# rasp_infrad.net
KiCad netlist of a schematic drawn in Altium Designer
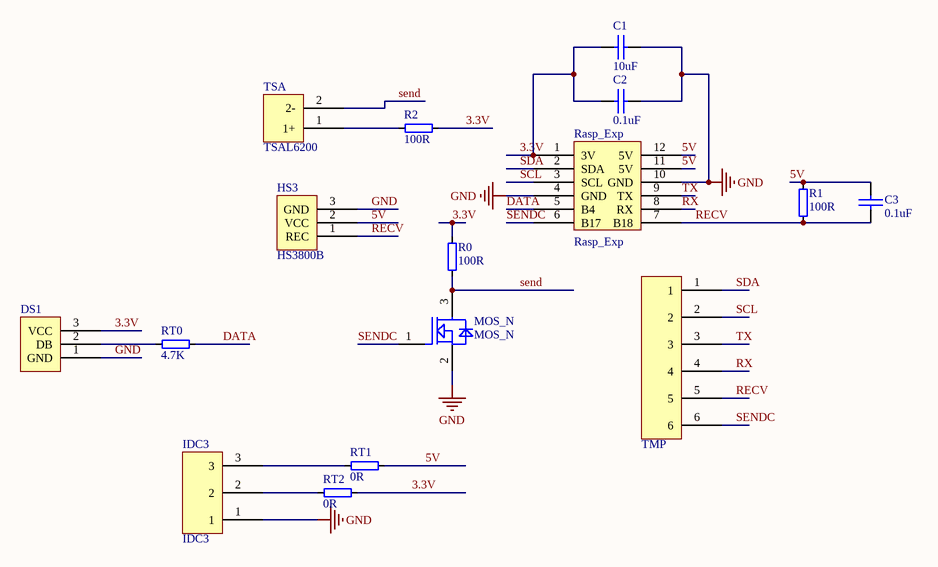
[diagram p0: rasp_infrad.SchDoc]

(export (version "E")
  (design (tool "Eeschema 10.0.6"))
  (components
    (comp (ref "C1")
      (value "10uF")
      (footprint "0805")
      (description "Capacitor")
      (libsource (lib "电容") (part "普通电容"))
    )
    (comp (ref "C2")
      (value "0.1uF")
      (footprint "0805")
      (description "Capacitor")
      (libsource (lib "电容") (part "普通电容"))
    )
    (comp (ref "C3")
      (value "0.1uF")
      (footprint "0805")
      (description "Capacitor")
      (libsource (lib "电容") (part "普通电容"))
    )
    (comp (ref "DS1")
      (value "DS1")
      (footprint "DS18B20")
      (description "数字温度传感器")
      (libsource (lib "Mo1-三角") (part "DS18B20"))
    )
    (comp (ref "HS3")
      (value "HS3800B")
      (footprint "HS0038B")
      (description "红外接收管")
      (libsource (lib "Mo1-三角") (part "HS3800B"))
    )
    (comp (ref "IDC3") (value "IDC3") (footprint "IDC3") (libsource (lib "Mo1-三角") (part "三脚引线孔")))
    (comp (ref "MOS_N") (value "MOS_N") (footprint "MOSN") (libsource (lib "Mo1-三角") (part "MOS_N")))
    (comp (ref "R0") (value "100R") (footprint "0805") (libsource (lib "电阻") (part "RES")))
    (comp (ref "R1") (value "100R") (footprint "0805") (libsource (lib "电阻") (part "RES")))
    (comp (ref "R2") (value "100R") (footprint "0805") (libsource (lib "电阻") (part "RES")))
    (comp (ref "Rasp_Exp")
      (value "Rasp_Exp")
      (footprint "Rasp_Exp")
      (libsource (lib "Mo1-三角") (part "Rasp_Exp"))
    )
    (comp (ref "RT0") (value "4.7K") (footprint "0805") (libsource (lib "电阻") (part "RES")))
    (comp (ref "RT1") (value "0R") (footprint "0805") (libsource (lib "电阻") (part "RES")))
    (comp (ref "RT2") (value "0R") (footprint "0805") (libsource (lib "电阻") (part "RES")))
    (comp (ref "TMP") (value "IDC6") (footprint "IDC6") (libsource (lib "Mo1-三角") (part "六脚引线孔")))
    (comp (ref "TSA") (value "TSAL6200") (footprint "TSAL6200") (libsource (lib "Mo1-三角") (part "TSAL6200")))
  )
  (nets
    (net (code "1") (name "/3.3V") (class "Default")
      (node (ref "C1") (pin "1") (pinfunction "1_1") (pintype "passive"))
      (node (ref "C2") (pin "1") (pinfunction "1_1") (pintype "passive"))
      (node (ref "DS1") (pin "3") (pinfunction "VCC_3") (pintype "passive"))
      (node (ref "R0") (pin "2") (pinfunction "2_2") (pintype "passive"))
      (node (ref "R2") (pin "1") (pinfunction "1_1") (pintype "passive"))
      (node (ref "RT2") (pin "1") (pinfunction "1_1") (pintype "passive"))
      (node (ref "Rasp_Exp") (pin "1") (pinfunction "3V_1") (pintype "passive"))
    )
    (net (code "2") (name "/5V") (class "Default")
      (node (ref "C3") (pin "2") (pinfunction "2_2") (pintype "passive"))
      (node (ref "HS3") (pin "2") (pinfunction "VCC_2") (pintype "passive"))
      (node (ref "R1") (pin "2") (pinfunction "2_2") (pintype "passive"))
      (node (ref "RT1") (pin "1") (pinfunction "1_1") (pintype "passive"))
      (node (ref "Rasp_Exp") (pin "11") (pinfunction "5V_11") (pintype "passive"))
      (node (ref "Rasp_Exp") (pin "12") (pinfunction "5V_12") (pintype "passive"))
    )
    (net (code "3") (name "/DATA") (class "Default")
      (node (ref "RT0") (pin "1") (pinfunction "1_1") (pintype "passive"))
      (node (ref "Rasp_Exp") (pin "5") (pinfunction "B4_5") (pintype "passive"))
    )
    (net (code "4") (name "/RECV") (class "Default")
      (node (ref "C3") (pin "1") (pinfunction "1_1") (pintype "passive"))
      (node (ref "HS3") (pin "1") (pinfunction "REC_1") (pintype "passive"))
      (node (ref "R1") (pin "1") (pinfunction "1_1") (pintype "passive"))
      (node (ref "Rasp_Exp") (pin "7") (pinfunction "B18_7") (pintype "passive"))
      (node (ref "TMP") (pin "5") (pinfunction "5_5") (pintype "open_collector"))
    )
    (net (code "5") (name "/RX") (class "Default")
      (node (ref "Rasp_Exp") (pin "8") (pinfunction "RX_8") (pintype "passive"))
      (node (ref "TMP") (pin "4") (pinfunction "4_4") (pintype "open_collector"))
    )
    (net (code "6") (name "/SCL") (class "Default")
      (node (ref "Rasp_Exp") (pin "3") (pinfunction "SCL_3") (pintype "passive"))
      (node (ref "TMP") (pin "2") (pinfunction "2_2") (pintype "open_collector"))
    )
    (net (code "7") (name "/SDA") (class "Default")
      (node (ref "Rasp_Exp") (pin "2") (pinfunction "SDA_2") (pintype "passive"))
      (node (ref "TMP") (pin "1") (pinfunction "1_1") (pintype "open_collector"))
    )
    (net (code "8") (name "/SENDC") (class "Default")
      (node (ref "MOS_N") (pin "1") (pinfunction "1_1") (pintype "passive"))
      (node (ref "Rasp_Exp") (pin "6") (pinfunction "B17_6") (pintype "passive"))
      (node (ref "TMP") (pin "6") (pinfunction "6_6") (pintype "open_collector"))
    )
    (net (code "9") (name "/TX") (class "Default")
      (node (ref "Rasp_Exp") (pin "9") (pinfunction "TX_9") (pintype "passive"))
      (node (ref "TMP") (pin "3") (pinfunction "3_3") (pintype "open_collector"))
    )
    (net (code "10") (name "/send") (class "Default")
      (node (ref "MOS_N") (pin "3") (pinfunction "3_3") (pintype "passive"))
      (node (ref "R0") (pin "1") (pinfunction "1_1") (pintype "passive"))
      (node (ref "TSA") (pin "2") (pinfunction "2-_2") (pintype "passive"))
    )
    (net (code "11") (name "GND") (class "Default")
      (node (ref "C1") (pin "2") (pinfunction "2_2") (pintype "passive"))
      (node (ref "C2") (pin "2") (pinfunction "2_2") (pintype "passive"))
      (node (ref "DS1") (pin "1") (pinfunction "GND_1") (pintype "passive"))
      (node (ref "HS3") (pin "3") (pinfunction "GND_3") (pintype "passive"))
      (node (ref "IDC3") (pin "1") (pinfunction "1_1") (pintype "open_collector"))
      (node (ref "MOS_N") (pin "2") (pinfunction "2_2") (pintype "passive"))
      (node (ref "Rasp_Exp") (pin "10") (pinfunction "GND_10") (pintype "passive"))
      (node (ref "Rasp_Exp") (pin "4") (pinfunction "GND_4") (pintype "passive"))
    )
    (net (code "12") (name "Net-(DS1-DB)") (class "Default")
      (node (ref "DS1") (pin "2") (pinfunction "DB_2") (pintype "passive"))
      (node (ref "RT0") (pin "2") (pinfunction "2_2") (pintype "passive"))
    )
    (net (code "13") (name "Net-(IDC3-Pad2)") (class "Default")
      (node (ref "IDC3") (pin "2") (pinfunction "2_2") (pintype "open_collector"))
      (node (ref "RT2") (pin "2") (pinfunction "2_2") (pintype "passive"))
    )
    (net (code "14") (name "Net-(IDC3-Pad3)") (class "Default")
      (node (ref "IDC3") (pin "3") (pinfunction "3_3") (pintype "open_collector"))
      (node (ref "RT1") (pin "2") (pinfunction "2_2") (pintype "passive"))
    )
    (net (code "15") (name "Net-(TSA-1+)") (class "Default")
      (node (ref "R2") (pin "2") (pinfunction "2_2") (pintype "passive"))
      (node (ref "TSA") (pin "1") (pinfunction "1+_1") (pintype "passive"))
    )
  )
)
